# PCB_Schematic.net
KiCad netlist of a schematic drawn in Altium Designer
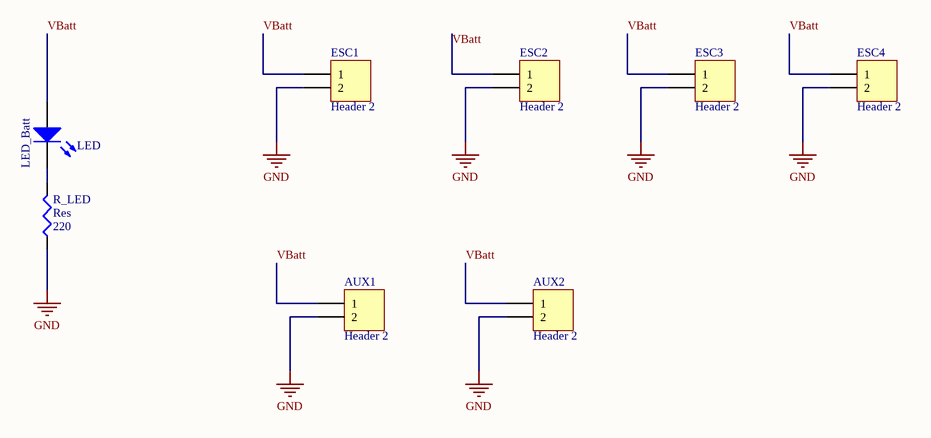
[diagram p0: PCB Schematic.SchDoc]

(export (version "E")
  (design (tool "Eeschema 10.0.6"))
  (components
    (comp (ref "AUX1")
      (value "Header 2")
      (footprint "HDR1X2")
      (description "Header, 2-Pin")
      (fields (field (name "PUBLISHER") "Altium Limited"))
      (libsource (lib "Miscellaneous Connectors") (part "Header 2"))
    )
    (comp (ref "AUX2")
      (value "Header 2")
      (footprint "HDR1X2")
      (description "Header, 2-Pin")
      (fields (field (name "PUBLISHER") "Altium Limited"))
      (libsource (lib "Miscellaneous Connectors") (part "Header 2"))
    )
    (comp (ref "ESC1")
      (value "Header 2")
      (footprint "Banana 3.5mm PowerPad")
      (description "Header, 2-Pin")
      (fields (field (name "PUBLISHER") "Altium Limited"))
      (libsource (lib "Miscellaneous Connectors") (part "Header 2"))
    )
    (comp (ref "ESC2")
      (value "Header 2")
      (footprint "Banana 3.5mm PowerPad")
      (description "Header, 2-Pin")
      (fields (field (name "PUBLISHER") "Altium Limited"))
      (libsource (lib "Miscellaneous Connectors") (part "Header 2"))
    )
    (comp (ref "ESC3")
      (value "Header 2")
      (footprint "Banana 3.5mm PowerPad")
      (description "Header, 2-Pin")
      (fields (field (name "PUBLISHER") "Altium Limited"))
      (libsource (lib "Miscellaneous Connectors") (part "Header 2"))
    )
    (comp (ref "ESC4")
      (value "Header 2")
      (footprint "Banana 3.5mm PowerPad")
      (description "Header, 2-Pin")
      (fields (field (name "PUBLISHER") "Altium Limited"))
      (libsource (lib "Miscellaneous Connectors") (part "Header 2"))
    )
    (comp (ref "LED_Batt")
      (value "LED")
      (footprint "6-0805_L")
      (description "Typical RED, GREEN, YELLOW, AMBER GaAs LED")
      (fields (field (name "PUBLISHER") "Altium Limited"))
      (libsource (lib "Miscellaneous Devices") (part "LED2"))
    )
    (comp (ref "R_LED")
      (value "Res")
      (footprint "6-0805_L")
      (description "Resistor")
      (fields (field (name "ALTIUM_VALUE") "220") (field (name "PUBLISHER") "Altium Limited"))
      (libsource (lib "Miscellaneous Devices") (part "Res3"))
    )
  )
  (nets
    (net (code "1") (name "/VBatt") (class "Default")
      (node (ref "AUX1") (pin "1") (pinfunction "1_1") (pintype "passive"))
      (node (ref "AUX2") (pin "1") (pinfunction "1_1") (pintype "passive"))
      (node (ref "ESC1") (pin "1") (pinfunction "1_1") (pintype "passive"))
      (node (ref "ESC2") (pin "1") (pinfunction "1_1") (pintype "passive"))
      (node (ref "ESC3") (pin "1") (pinfunction "1_1") (pintype "passive"))
      (node (ref "ESC4") (pin "1") (pinfunction "1_1") (pintype "passive"))
      (node (ref "LED_Batt") (pin "1") (pinfunction "A_1") (pintype "passive"))
    )
    (net (code "2") (name "GND") (class "Default")
      (node (ref "AUX1") (pin "2") (pinfunction "2_2") (pintype "passive"))
      (node (ref "AUX2") (pin "2") (pinfunction "2_2") (pintype "passive"))
      (node (ref "ESC1") (pin "2") (pinfunction "2_2") (pintype "passive"))
      (node (ref "ESC2") (pin "2") (pinfunction "2_2") (pintype "passive"))
      (node (ref "ESC3") (pin "2") (pinfunction "2_2") (pintype "passive"))
      (node (ref "ESC4") (pin "2") (pinfunction "2_2") (pintype "passive"))
      (node (ref "R_LED") (pin "1") (pinfunction "1_1") (pintype "passive"))
    )
    (net (code "3") (name "Net-(LED_Batt-K)") (class "Default")
      (node (ref "LED_Batt") (pin "2") (pinfunction "K_2") (pintype "passive"))
      (node (ref "R_LED") (pin "2") (pinfunction "2_2") (pintype "passive"))
    )
  )
)
